# vfd_power.net
KiCad netlist of a schematic drawn in Altium Designer
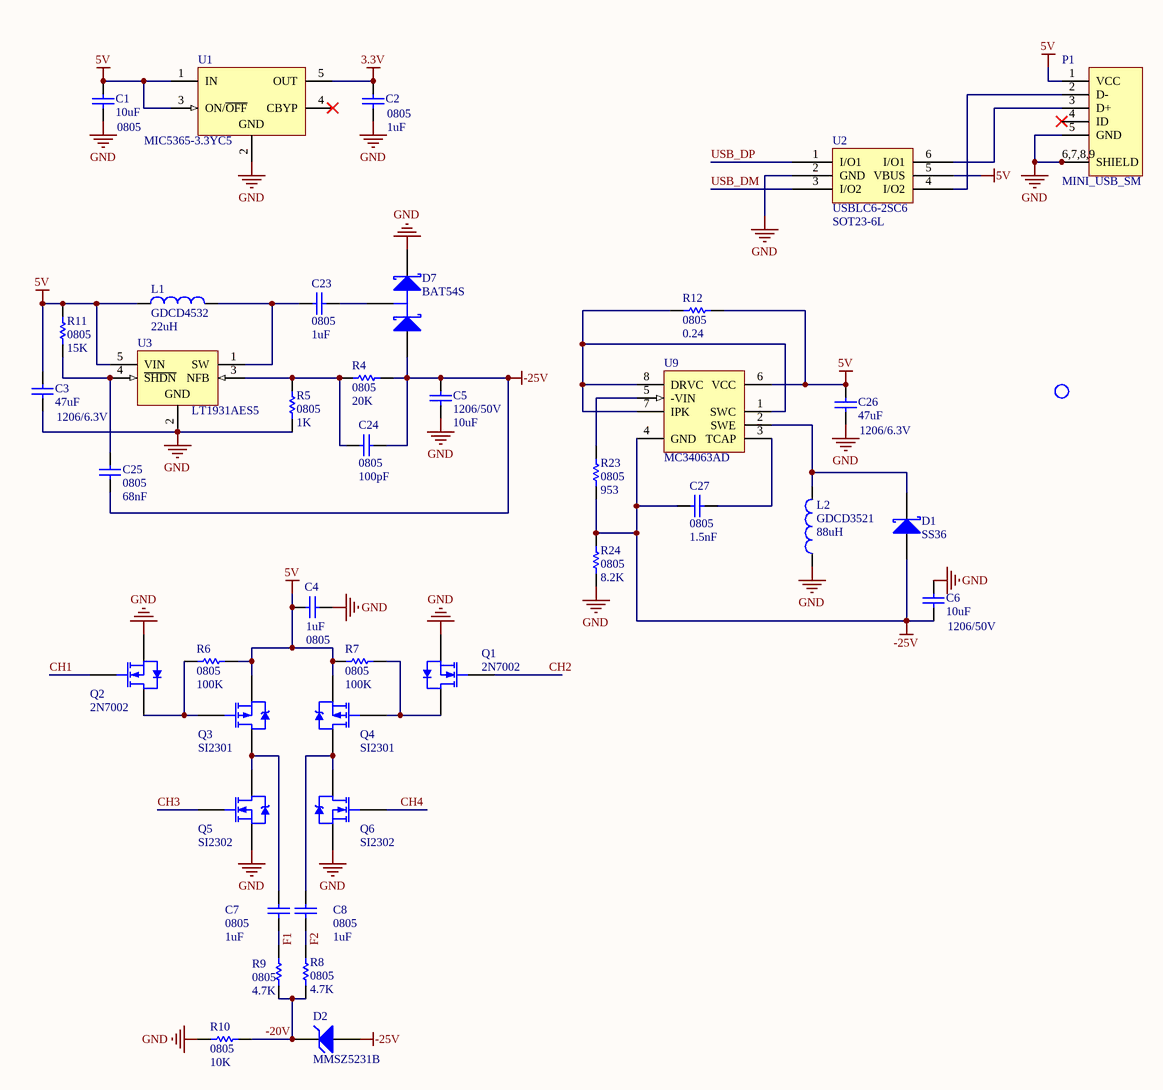
[diagram p0: vfd_power.SchDoc]

(export (version "E")
  (design (tool "Eeschema 10.0.6"))
  (components
    (comp (ref "C1")
      (value "0805")
      (footprint "6-0805_N")
      (description "Capacitor")
      (fields (field (name "ALTIUM_VALUE") "10uF") (field (name "PUBLISHER") "Altium Limited"))
      (libsource (lib "Miscellaneous Devices") (part "Cap"))
    )
    (comp (ref "C2")
      (value "0805")
      (footprint "6-0805_N")
      (description "Capacitor")
      (fields (field (name "ALTIUM_VALUE") "1uF") (field (name "PUBLISHER") "Altium Limited"))
      (libsource (lib "Miscellaneous Devices") (part "Cap"))
    )
    (comp (ref "C3")
      (value "1206/6.3V")
      (footprint "C1206")
      (description "Capacitor")
      (fields (field (name "ALTIUM_VALUE") "47uF") (field (name "PUBLISHER") "Altium Limited"))
      (libsource (lib "Miscellaneous Devices") (part "Cap"))
    )
    (comp (ref "C4")
      (value "0805")
      (footprint "6-0805_N")
      (description "Capacitor")
      (fields (field (name "ALTIUM_VALUE") "1uF") (field (name "PUBLISHER") "Altium Limited"))
      (libsource (lib "Miscellaneous Devices") (part "Cap"))
    )
    (comp (ref "C5")
      (value "1206/50V")
      (footprint "C1206")
      (description "Capacitor")
      (fields (field (name "ALTIUM_VALUE") "10uF") (field (name "PUBLISHER") "Altium Limited"))
      (libsource (lib "Miscellaneous Devices") (part "Cap"))
    )
    (comp (ref "C6")
      (value "1206/50V")
      (footprint "C1206")
      (description "Capacitor")
      (fields (field (name "ALTIUM_VALUE") "10uF") (field (name "PUBLISHER") "Altium Limited"))
      (libsource (lib "Miscellaneous Devices") (part "Cap"))
    )
    (comp (ref "C7")
      (value "0805")
      (footprint "6-0805_N")
      (description "Capacitor")
      (fields (field (name "ALTIUM_VALUE") "1uF") (field (name "PUBLISHER") "Altium Limited"))
      (libsource (lib "Miscellaneous Devices") (part "Cap"))
    )
    (comp (ref "C8")
      (value "0805")
      (footprint "6-0805_N")
      (description "Capacitor")
      (fields (field (name "ALTIUM_VALUE") "1uF") (field (name "PUBLISHER") "Altium Limited"))
      (libsource (lib "Miscellaneous Devices") (part "Cap"))
    )
    (comp (ref "C23")
      (value "0805")
      (footprint "6-0805_N")
      (description "Capacitor")
      (fields (field (name "ALTIUM_VALUE") "1uF") (field (name "PUBLISHER") "Altium Limited"))
      (libsource (lib "Miscellaneous Devices") (part "Cap"))
    )
    (comp (ref "C24")
      (value "0805")
      (footprint "6-0805_N")
      (description "Capacitor")
      (fields (field (name "ALTIUM_VALUE") "100pF") (field (name "PUBLISHER") "Altium Limited"))
      (libsource (lib "Miscellaneous Devices") (part "Cap"))
    )
    (comp (ref "C25")
      (value "0805")
      (footprint "6-0805_N")
      (description "Capacitor")
      (fields (field (name "ALTIUM_VALUE") "68nF") (field (name "PUBLISHER") "Altium Limited"))
      (libsource (lib "Miscellaneous Devices") (part "Cap"))
    )
    (comp (ref "C26")
      (value "1206/6.3V")
      (footprint "C1206")
      (description "Capacitor")
      (fields (field (name "ALTIUM_VALUE") "47uF") (field (name "PUBLISHER") "Altium Limited"))
      (libsource (lib "Miscellaneous Devices") (part "Cap"))
    )
    (comp (ref "C27")
      (value "0805")
      (footprint "6-0805_N")
      (description "Capacitor")
      (fields (field (name "ALTIUM_VALUE") "1.5nF") (field (name "PUBLISHER") "Altium Limited"))
      (libsource (lib "Miscellaneous Devices") (part "Cap"))
    )
    (comp (ref "D1")
      (value "SS36")
      (footprint "SMA")
      (description "Schottky Diode")
      (fields (field (name "PUBLISHER") "Altium Limited"))
      (libsource (lib "Miscellaneous Devices") (part "D Schottky"))
    )
    (comp (ref "D2")
      (value "MMSZ5231B")
      (footprint "SOD-123")
      (description "Zener Diode")
      (fields (field (name "PUBLISHER") "Altium Limited"))
      (libsource (lib "Miscellaneous Devices") (part "D Zener"))
    )
    (comp (ref "D7")
      (value "BAT54S")
      (footprint "SOT23_N")
      (description "Schottky Barrier Double Diode")
      (fields (field (name "PUBLISHER") "Altium Limited"))
      (libsource (lib "Philips Discrete Diode - Schottky") (part "BAT54S"))
    )
    (comp (ref "G1") (value "ESD Label") (footprint "ESD") (libsource (lib "常用封装库") (part "g固定过孔")))
    (comp (ref "L1")
      (value "GDCD4532")
      (footprint "GDCD4532")
      (description "Inductor")
      (fields (field (name "ALTIUM_VALUE") "22uH") (field (name "PUBLISHER") "Altium Limited"))
      (libsource (lib "Miscellaneous Devices") (part "Inductor"))
    )
    (comp (ref "L2")
      (value "GDCD3521")
      (footprint "GDCD3521")
      (description "Inductor")
      (fields (field (name "ALTIUM_VALUE") "88uH") (field (name "PUBLISHER") "Altium Limited"))
      (libsource (lib "Miscellaneous Devices") (part "Inductor"))
    )
    (comp (ref "P1")
      (value "MINI_USB_SM")
      (footprint "USB/SM0.8-6H5")
      (libsource (lib "MINE") (part "MINI_USB_SM"))
    )
    (comp (ref "Q1")
      (value "2N7002")
      (footprint "SOT-23")
      (description "N-channel Enhancement Mode Field-effect Transistor")
      (fields (field (name "PUBLISHER") "Altium Limited"))
      (libsource (lib "Philips Discrete MOSFET - Low Power") (part "2N7002"))
    )
    (comp (ref "Q2")
      (value "2N7002")
      (footprint "SOT-23")
      (description "N-channel Enhancement Mode Field-effect Transistor")
      (fields (field (name "PUBLISHER") "Altium Limited"))
      (libsource (lib "Philips Discrete MOSFET - Low Power") (part "2N7002"))
    )
    (comp (ref "Q3")
      (value "SI2301")
      (footprint "SOT-23")
      (description "P-Channel Power MOSFET")
      (fields (field (name "PUBLISHER") "Altium Limited"))
      (libsource (lib "Miscellaneous Devices") (part "PMOS-2"))
    )
    (comp (ref "Q4")
      (value "SI2301")
      (footprint "SOT-23")
      (description "P-Channel Power MOSFET")
      (fields (field (name "PUBLISHER") "Altium Limited"))
      (libsource (lib "Miscellaneous Devices") (part "PMOS-2"))
    )
    (comp (ref "Q5")
      (value "SI2302")
      (footprint "SOT-23")
      (description "N-Channel Power MOSFET")
      (fields (field (name "PUBLISHER") "Altium Limited"))
      (libsource (lib "Miscellaneous Devices") (part "NMOS-2"))
    )
    (comp (ref "Q6")
      (value "SI2302")
      (footprint "SOT-23")
      (description "N-Channel Power MOSFET")
      (fields (field (name "PUBLISHER") "Altium Limited"))
      (libsource (lib "Miscellaneous Devices") (part "NMOS-2"))
    )
    (comp (ref "R4")
      (value "0805")
      (footprint "6-0805_N")
      (description "Resistor")
      (fields (field (name "ALTIUM_VALUE") "20K") (field (name "PUBLISHER") "Altium Limited"))
      (libsource (lib "Miscellaneous Devices") (part "Res1"))
    )
    (comp (ref "R5")
      (value "0805")
      (footprint "6-0805_N")
      (description "Resistor")
      (fields (field (name "ALTIUM_VALUE") "1K") (field (name "PUBLISHER") "Altium Limited"))
      (libsource (lib "Miscellaneous Devices") (part "Res1"))
    )
    (comp (ref "R6")
      (value "0805")
      (footprint "6-0805_N")
      (description "Resistor")
      (fields (field (name "ALTIUM_VALUE") "100K") (field (name "PUBLISHER") "Altium Limited"))
      (libsource (lib "Miscellaneous Devices") (part "Res1"))
    )
    (comp (ref "R7")
      (value "0805")
      (footprint "6-0805_N")
      (description "Resistor")
      (fields (field (name "ALTIUM_VALUE") "100K") (field (name "PUBLISHER") "Altium Limited"))
      (libsource (lib "Miscellaneous Devices") (part "Res1"))
    )
    (comp (ref "R8")
      (value "0805")
      (footprint "6-0805_N")
      (description "Resistor")
      (fields (field (name "ALTIUM_VALUE") "4.7K") (field (name "PUBLISHER") "Altium Limited"))
      (libsource (lib "Miscellaneous Devices") (part "Res1"))
    )
    (comp (ref "R9")
      (value "0805")
      (footprint "6-0805_N")
      (description "Resistor")
      (fields (field (name "ALTIUM_VALUE") "4.7K") (field (name "PUBLISHER") "Altium Limited"))
      (libsource (lib "Miscellaneous Devices") (part "Res1"))
    )
    (comp (ref "R10")
      (value "0805")
      (footprint "6-0805_N")
      (description "Resistor")
      (fields (field (name "ALTIUM_VALUE") "10K") (field (name "PUBLISHER") "Altium Limited"))
      (libsource (lib "Miscellaneous Devices") (part "Res1"))
    )
    (comp (ref "R11")
      (value "0805")
      (footprint "6-0805_N")
      (description "Resistor")
      (fields (field (name "ALTIUM_VALUE") "15K") (field (name "PUBLISHER") "Altium Limited"))
      (libsource (lib "Miscellaneous Devices") (part "Res1"))
    )
    (comp (ref "R12")
      (value "0805")
      (footprint "6-0805_N")
      (description "Resistor")
      (fields (field (name "ALTIUM_VALUE") "0.24") (field (name "PUBLISHER") "Altium Limited"))
      (libsource (lib "Miscellaneous Devices") (part "Res1"))
    )
    (comp (ref "R23")
      (value "0805")
      (footprint "6-0805_N")
      (description "Resistor")
      (fields (field (name "ALTIUM_VALUE") "953") (field (name "PUBLISHER") "Altium Limited"))
      (libsource (lib "Miscellaneous Devices") (part "Res1"))
    )
    (comp (ref "R24")
      (value "0805")
      (footprint "6-0805_N")
      (description "Resistor")
      (fields (field (name "ALTIUM_VALUE") "8.2K") (field (name "PUBLISHER") "Altium Limited"))
      (libsource (lib "Miscellaneous Devices") (part "Res1"))
    )
    (comp (ref "U1")
      (value "MIC5365-3.3YC5")
      (footprint "SC70-5_N")
      (description "Micropower 150 mA Low-Noise Ultra Low-Dropout Regulator, 5-pin SOT-323, Pb-Free")
      (fields
        (field (name "MANUFACTURER") "National Semiconductor")
        (field (name "PUBLISHER") "Altium Limited")
      )
      (libsource (lib "altium-import") (part "root_0_LP2985AIM5-3.3/NOPB_"))
    )
    (comp (ref "U2")
      (value "USBLC6-2SC6")
      (footprint "SOT-23_A_N")
      (fields (field (name "PACKAGEREFERENCE") "SOT23-6L"))
      (libsource (lib "USB") (part "Component_1"))
    )
    (comp (ref "U3")
      (value "LT1931AES5")
      (footprint "S5-T_N")
      (description "2.2MHz Inverting Current Mode DC/DC Converter")
      (fields (field (name "PUBLISHER") "Altium Limited"))
      (libsource (lib "LT Power Mgt DC-DC Converter") (part "LT1931AES5"))
    )
    (comp (ref "U9")
      (value "MC34063AD")
      (footprint "751-02_N")
      (description "DC-to-DC Converter Control Circuit")
      (fields (field (name "PUBLISHER") "Altium Limited"))
      (libsource (lib "Motorola Power Mgt DC-DC Converter") (part "MC34063AD"))
    )
  )
  (nets
    (net (code "1") (name "-25V") (class "Default")
      (node (ref "C24") (pin "1") (pinfunction "1_1") (pintype "passive"))
      (node (ref "C25") (pin "2") (pinfunction "2_2") (pintype "passive"))
      (node (ref "C27") (pin "2") (pinfunction "2_2") (pintype "passive"))
      (node (ref "C5") (pin "1") (pinfunction "1_1") (pintype "passive"))
      (node (ref "C6") (pin "1") (pinfunction "1_1") (pintype "passive"))
      (node (ref "D1") (pin "1") (pinfunction "A_1") (pintype "passive"))
      (node (ref "D2") (pin "1") (pinfunction "A_1") (pintype "passive"))
      (node (ref "D7") (pin "1") (pinfunction "A_1") (pintype "passive"))
      (node (ref "R23") (pin "2") (pinfunction "2_2") (pintype "passive"))
      (node (ref "R24") (pin "1") (pinfunction "1_1") (pintype "passive"))
      (node (ref "R4") (pin "1") (pinfunction "1_1") (pintype "passive"))
      (node (ref "U9") (pin "4") (pinfunction "GND_4") (pintype "power_in"))
    )
    (net (code "2") (name "/-20V") (class "Default")
      (node (ref "D2") (pin "2") (pinfunction "K_2") (pintype "passive"))
      (node (ref "R10") (pin "2") (pinfunction "2_2") (pintype "passive"))
      (node (ref "R8") (pin "2") (pinfunction "2_2") (pintype "passive"))
      (node (ref "R9") (pin "2") (pinfunction "2_2") (pintype "passive"))
    )
    (net (code "3") (name "/CH1") (class "Default")
      (node (ref "Q2") (pin "1") (pinfunction "G_1") (pintype "passive"))
    )
    (net (code "4") (name "/CH2") (class "Default")
      (node (ref "Q1") (pin "1") (pinfunction "G_1") (pintype "passive"))
    )
    (net (code "5") (name "/CH3") (class "Default")
      (node (ref "Q5") (pin "1") (pinfunction "G_1") (pintype "passive"))
    )
    (net (code "6") (name "/CH4") (class "Default")
      (node (ref "Q6") (pin "1") (pinfunction "G_1") (pintype "passive"))
    )
    (net (code "7") (name "/F1") (class "Default")
      (node (ref "C7") (pin "1") (pinfunction "1_1") (pintype "passive"))
      (node (ref "R9") (pin "1") (pinfunction "1_1") (pintype "passive"))
    )
    (net (code "8") (name "/F2") (class "Default")
      (node (ref "C8") (pin "1") (pinfunction "1_1") (pintype "passive"))
      (node (ref "R8") (pin "1") (pinfunction "1_1") (pintype "passive"))
    )
    (net (code "9") (name "/USB_DM") (class "Default")
      (node (ref "U2") (pin "3") (pinfunction "I/O2_3") (pintype "passive"))
    )
    (net (code "10") (name "/USB_DP") (class "Default")
      (node (ref "U2") (pin "1") (pinfunction "I/O1_1") (pintype "passive"))
    )
    (net (code "11") (name "3.3V") (class "Default")
      (node (ref "C2") (pin "2") (pinfunction "2_2") (pintype "passive"))
      (node (ref "U1") (pin "5") (pinfunction "OUT_5") (pintype "power_in"))
    )
    (net (code "12") (name "5V") (class "Default")
      (node (ref "C1") (pin "2") (pinfunction "2_2") (pintype "passive"))
      (node (ref "C26") (pin "2") (pinfunction "2_2") (pintype "passive"))
      (node (ref "C3") (pin "2") (pinfunction "2_2") (pintype "passive"))
      (node (ref "C4") (pin "2") (pinfunction "2_2") (pintype "passive"))
      (node (ref "L1") (pin "1") (pinfunction "1_1") (pintype "passive"))
      (node (ref "P1") (pin "1") (pinfunction "VCC_1") (pintype "passive"))
      (node (ref "Q3") (pin "2") (pinfunction "S_2") (pintype "passive"))
      (node (ref "Q4") (pin "2") (pinfunction "S_2") (pintype "passive"))
      (node (ref "R11") (pin "1") (pinfunction "1_1") (pintype "passive"))
      (node (ref "R12") (pin "1") (pinfunction "1_1") (pintype "passive"))
      (node (ref "R6") (pin "1") (pinfunction "1_1") (pintype "passive"))
      (node (ref "R7") (pin "2") (pinfunction "2_2") (pintype "passive"))
      (node (ref "U1") (pin "1") (pinfunction "IN_1") (pintype "power_in"))
      (node (ref "U1") (pin "3") (pinfunction "ON/~{OFF}_3") (pintype "input"))
      (node (ref "U2") (pin "5") (pinfunction "VBUS_5") (pintype "passive"))
      (node (ref "U3") (pin "5") (pinfunction "VIN_5") (pintype "power_in"))
      (node (ref "U9") (pin "6") (pinfunction "VCC_6") (pintype "power_in"))
    )
    (net (code "13") (name "GND") (class "Default")
      (node (ref "C1") (pin "1") (pinfunction "1_1") (pintype "passive"))
      (node (ref "C2") (pin "1") (pinfunction "1_1") (pintype "passive"))
      (node (ref "C26") (pin "1") (pinfunction "1_1") (pintype "passive"))
      (node (ref "C3") (pin "1") (pinfunction "1_1") (pintype "passive"))
      (node (ref "C4") (pin "1") (pinfunction "1_1") (pintype "passive"))
      (node (ref "C5") (pin "2") (pinfunction "2_2") (pintype "passive"))
      (node (ref "C6") (pin "2") (pinfunction "2_2") (pintype "passive"))
      (node (ref "D7") (pin "2") (pinfunction "K_2") (pintype "passive"))
      (node (ref "L2") (pin "1") (pinfunction "1_1") (pintype "passive"))
      (node (ref "P1") (pin "5") (pinfunction "GND_5") (pintype "passive"))
      (node (ref "P1") (pin "6") (pinfunction "SHIELD_6") (pintype "passive"))
      (node (ref "P1") (pin "7") (pinfunction "SHIELD_7") (pintype "passive"))
      (node (ref "P1") (pin "8") (pinfunction "SHIELD_8") (pintype "passive"))
      (node (ref "P1") (pin "9") (pinfunction "SHIELD_9") (pintype "passive"))
      (node (ref "Q1") (pin "2") (pinfunction "S_2") (pintype "passive"))
      (node (ref "Q2") (pin "2") (pinfunction "S_2") (pintype "passive"))
      (node (ref "Q5") (pin "2") (pinfunction "S_2") (pintype "passive"))
      (node (ref "Q6") (pin "2") (pinfunction "S_2") (pintype "passive"))
      (node (ref "R10") (pin "1") (pinfunction "1_1") (pintype "passive"))
      (node (ref "R24") (pin "2") (pinfunction "2_2") (pintype "passive"))
      (node (ref "R5") (pin "1") (pinfunction "1_1") (pintype "passive"))
      (node (ref "U1") (pin "2") (pinfunction "GND_2") (pintype "power_in"))
      (node (ref "U2") (pin "2") (pinfunction "GND_2") (pintype "passive"))
      (node (ref "U3") (pin "2") (pinfunction "GND_2") (pintype "power_in"))
    )
    (net (code "14") (name "Net-(D1-K)") (class "Default")
      (node (ref "D1") (pin "2") (pinfunction "K_2") (pintype "passive"))
      (node (ref "L2") (pin "2") (pinfunction "2_2") (pintype "passive"))
      (node (ref "U9") (pin "2") (pinfunction "SWE_2") (pintype "open_emitter"))
    )
    (net (code "15") (name "Net-(D7-C)") (class "Default")
      (node (ref "C23") (pin "1") (pinfunction "1_1") (pintype "passive"))
      (node (ref "D7") (pin "3") (pinfunction "C_3") (pintype "passive"))
    )
    (net (code "16") (name "Net-(P1-D+)") (class "Default")
      (node (ref "P1") (pin "3") (pinfunction "D+_3") (pintype "passive"))
      (node (ref "U2") (pin "6") (pinfunction "I/O1_6") (pintype "passive"))
    )
    (net (code "17") (name "Net-(P1-D-)") (class "Default")
      (node (ref "P1") (pin "2") (pinfunction "D-_2") (pintype "passive"))
      (node (ref "U2") (pin "4") (pinfunction "I/O2_4") (pintype "passive"))
    )
    (net (code "18") (name "Net-(Q1-D)") (class "Default")
      (node (ref "Q1") (pin "3") (pinfunction "D_3") (pintype "passive"))
      (node (ref "Q4") (pin "1") (pinfunction "G_1") (pintype "passive"))
      (node (ref "R7") (pin "1") (pinfunction "1_1") (pintype "passive"))
    )
    (net (code "19") (name "Net-(Q2-D)") (class "Default")
      (node (ref "Q2") (pin "3") (pinfunction "D_3") (pintype "passive"))
      (node (ref "Q3") (pin "1") (pinfunction "G_1") (pintype "passive"))
      (node (ref "R6") (pin "2") (pinfunction "2_2") (pintype "passive"))
    )
    (net (code "20") (name "Net-(Q3-D)") (class "Default")
      (node (ref "C7") (pin "2") (pinfunction "2_2") (pintype "passive"))
      (node (ref "Q3") (pin "3") (pinfunction "D_3") (pintype "passive"))
      (node (ref "Q5") (pin "3") (pinfunction "D_3") (pintype "passive"))
    )
    (net (code "21") (name "Net-(Q4-D)") (class "Default")
      (node (ref "C8") (pin "2") (pinfunction "2_2") (pintype "passive"))
      (node (ref "Q4") (pin "3") (pinfunction "D_3") (pintype "passive"))
      (node (ref "Q6") (pin "3") (pinfunction "D_3") (pintype "passive"))
    )
    (net (code "22") (name "Net-(U3-NFB)") (class "Default")
      (node (ref "C24") (pin "2") (pinfunction "2_2") (pintype "passive"))
      (node (ref "R4") (pin "2") (pinfunction "2_2") (pintype "passive"))
      (node (ref "R5") (pin "2") (pinfunction "2_2") (pintype "passive"))
      (node (ref "U3") (pin "3") (pinfunction "NFB_3") (pintype "input"))
    )
    (net (code "23") (name "Net-(U3-SW)") (class "Default")
      (node (ref "C23") (pin "2") (pinfunction "2_2") (pintype "passive"))
      (node (ref "L1") (pin "2") (pinfunction "2_2") (pintype "passive"))
      (node (ref "U3") (pin "1") (pinfunction "SW_1") (pintype "passive"))
    )
    (net (code "24") (name "Net-(U3-~{SHDN})") (class "Default")
      (node (ref "C25") (pin "1") (pinfunction "1_1") (pintype "passive"))
      (node (ref "R11") (pin "2") (pinfunction "2_2") (pintype "passive"))
      (node (ref "U3") (pin "4") (pinfunction "~{SHDN}_4") (pintype "input"))
    )
    (net (code "25") (name "Net-(U9--VIN)") (class "Default")
      (node (ref "R23") (pin "1") (pinfunction "1_1") (pintype "passive"))
      (node (ref "U9") (pin "5") (pinfunction "-VIN_5") (pintype "input"))
    )
    (net (code "26") (name "Net-(U9-DRVC)") (class "Default")
      (node (ref "R12") (pin "2") (pinfunction "2_2") (pintype "passive"))
      (node (ref "U9") (pin "1") (pinfunction "SWC_1") (pintype "open_collector"))
      (node (ref "U9") (pin "7") (pinfunction "IPK_7") (pintype "passive"))
      (node (ref "U9") (pin "8") (pinfunction "DRVC_8") (pintype "open_collector"))
    )
    (net (code "27") (name "Net-(U9-TCAP)") (class "Default")
      (node (ref "C27") (pin "1") (pinfunction "1_1") (pintype "passive"))
      (node (ref "U9") (pin "3") (pinfunction "TCAP_3") (pintype "passive"))
    )
    (net (code "28") (name "unconnected-(P1-ID-Pad4)") (class "Default")
      (node (ref "P1") (pin "4") (pinfunction "ID_4") (pintype "passive+no_connect"))
    )
    (net (code "29") (name "unconnected-(U1-CBYP-Pad4)") (class "Default")
      (node (ref "U1") (pin "4") (pinfunction "CBYP_4") (pintype "passive+no_connect"))
    )
  )
)
